# 5v_LP_Test_Mod.net
KiCad netlist of a schematic drawn in EAGLE
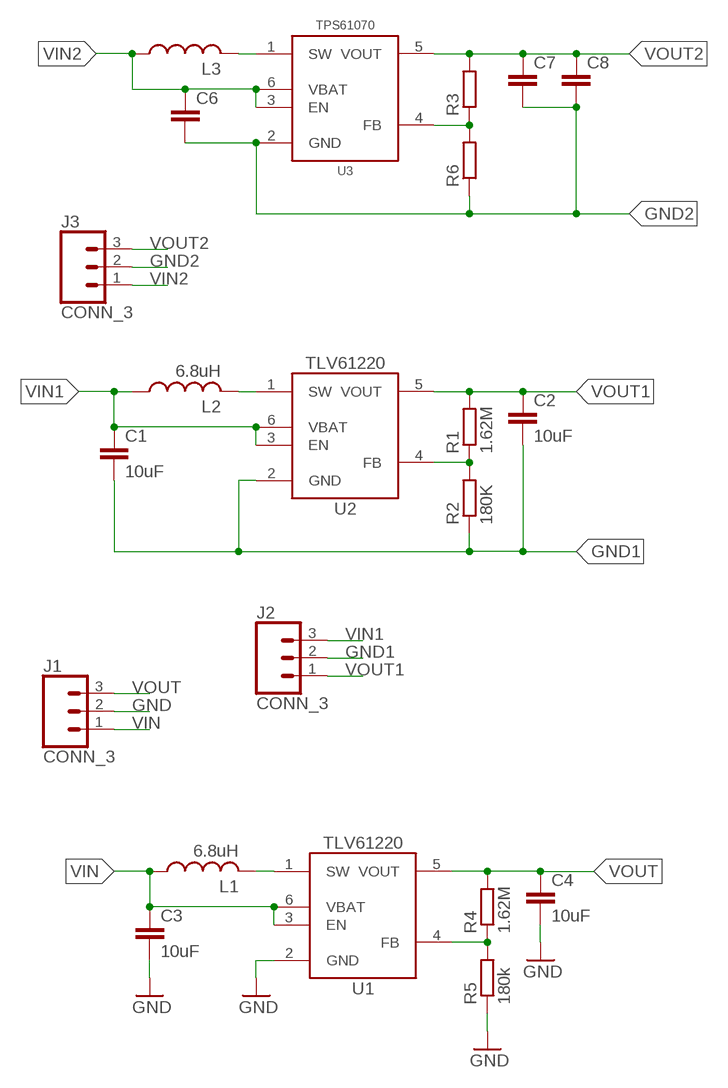
[diagram p0: schematic, sheet 1]

(export (version "E")
  (design (tool "Eeschema 10.0.6"))
  (components
    (comp (ref "C1")
      (value "10uF")
      (footprint "eagle-import:C0805")
      (fields (field (name "MF") "Murata") (field (name "MPN") "GRM21BR61C106KE15K"))
      (libsource (lib "eagle-import") (part "C-EUC080510UF"))
    )
    (comp (ref "C2")
      (value "10uF")
      (footprint "eagle-import:C0805")
      (fields (field (name "MF") "Murata") (field (name "MPN") "GRM21BR61C106KE15K"))
      (libsource (lib "eagle-import") (part "C-EUC080510UF"))
    )
    (comp (ref "C3")
      (value "10uF")
      (footprint "eagle-import:C0805")
      (fields (field (name "MF") "Murata") (field (name "MPN") "GRM21BR61C106KE15K"))
      (libsource (lib "eagle-import") (part "C-EUC080510UF"))
    )
    (comp (ref "C4")
      (value "10uF")
      (footprint "eagle-import:C0805")
      (fields (field (name "MF") "Murata") (field (name "MPN") "GRM21BR61C106KE15K"))
      (libsource (lib "eagle-import") (part "C-EUC080510UF"))
    )
    (comp (ref "C6")
      (value "C-EUC0805")
      (footprint "eagle-import:C0805")
      (libsource (lib "eagle-import") (part "C-EUC0805"))
    )
    (comp (ref "C7")
      (value "C-EUC0603")
      (footprint "eagle-import:C0603")
      (libsource (lib "eagle-import") (part "C-EUC0603"))
    )
    (comp (ref "C8")
      (value "C-EUC0603")
      (footprint "eagle-import:C0603")
      (libsource (lib "eagle-import") (part "C-EUC0603"))
    )
    (comp (ref "J1")
      (value "CONN_3")
      (footprint "eagle-import:1X03")
      (libsource (lib "eagle-import") (part "CONN_3"))
    )
    (comp (ref "J2")
      (value "CONN_3")
      (footprint "eagle-import:1X03")
      (libsource (lib "eagle-import") (part "CONN_3"))
    )
    (comp (ref "J3")
      (value "CONN_3")
      (footprint "eagle-import:1X03")
      (libsource (lib "eagle-import") (part "CONN_3"))
    )
    (comp (ref "L1")
      (value "6.8uH")
      (footprint "eagle-import:1008")
      (fields (field (name "MF") "Wurth") (field (name "MPN") "74438323068"))
      (libsource (lib "eagle-import") (part "INDUCTOR1008"))
    )
    (comp (ref "L2")
      (value "6.8uH")
      (footprint "eagle-import:1008")
      (libsource (lib "eagle-import") (part "INDUCTOR1008"))
    )
    (comp (ref "L3")
      (value "INDUCTORTPC_3.8X3.8")
      (footprint "eagle-import:WE-TPC(3.8X3.8)")
      (libsource (lib "eagle-import") (part "INDUCTORTPC_3.8X3.8"))
    )
    (comp (ref "R1")
      (value "1.62M")
      (footprint "eagle-import:R0603")
      (fields (field (name "MF") "Yageo"))
      (libsource (lib "eagle-import") (part "R-EU_R0603"))
    )
    (comp (ref "R2")
      (value "180K")
      (footprint "eagle-import:R0603")
      (fields (field (name "MF") "Yageo"))
      (libsource (lib "eagle-import") (part "R-EU_R0603"))
    )
    (comp (ref "R3")
      (value "R-EU_R0603")
      (footprint "eagle-import:R0603")
      (fields (field (name "MF") "Yageo"))
      (libsource (lib "eagle-import") (part "R-EU_R0603"))
    )
    (comp (ref "R4")
      (value "1.62M")
      (footprint "eagle-import:R0603")
      (fields (field (name "MF") "Stackpole") (field (name "MPN") "RMCF0603FT1M62"))
      (libsource (lib "eagle-import") (part "R-EU_R06031.62M"))
    )
    (comp (ref "R5")
      (value "180k")
      (footprint "eagle-import:R0603")
      (fields (field (name "MF") "Panasonic") (field (name "MPN") "ERJ-3EKF1803V"))
      (libsource (lib "eagle-import") (part "R-EU_R0603180K"))
    )
    (comp (ref "R6")
      (value "R-EU_R0603")
      (footprint "eagle-import:R0603")
      (fields (field (name "MF") "Yageo"))
      (libsource (lib "eagle-import") (part "R-EU_R0603"))
    )
    (comp (ref "U1")
      (value "TLV61220DBV")
      (footprint "eagle-import:DBV_R-PDSO-G6")
      (fields (field (name "MF") "TI") (field (name "MPN") "TLV61220DBVR"))
      (libsource (lib "eagle-import") (part "TLV61220DBV"))
    )
    (comp (ref "U2")
      (value "TLV61220DBV")
      (footprint "eagle-import:DBV_R-PDSO-G6")
      (fields (field (name "MF") "TI") (field (name "MPN") "TLV61220DBVR"))
      (libsource (lib "eagle-import") (part "TLV61220DBV"))
    )
    (comp (ref "U3")
      (value "TPS61070DDC")
      (footprint "eagle-import:DDC_R-PDSO-G6")
      (fields (field (name "DISP") "TPS61070") (field (name "MF") "TI") (field (name "MPN") "TPS61070DDCR"))
      (libsource (lib "eagle-import") (part "TPS6107DDC0"))
    )
  )
  (nets
    (net (code "1") (name "GND") (class "Default")
      (node (ref "C3") (pin "2") (pinfunction "2_2") (pintype "passive"))
      (node (ref "C4") (pin "2") (pinfunction "2_2") (pintype "passive"))
      (node (ref "J1") (pin "2") (pinfunction "2_2") (pintype "passive"))
      (node (ref "R5") (pin "1") (pinfunction "1_1") (pintype "passive"))
      (node (ref "U1") (pin "2") (pinfunction "GND_2") (pintype "power_in"))
    )
    (net (code "2") (name "GND1") (class "Default")
      (node (ref "C1") (pin "2") (pinfunction "2_2") (pintype "passive"))
      (node (ref "C2") (pin "2") (pinfunction "2_2") (pintype "passive"))
      (node (ref "J2") (pin "2") (pinfunction "2_2") (pintype "passive"))
      (node (ref "R2") (pin "1") (pinfunction "1_1") (pintype "passive"))
      (node (ref "U2") (pin "2") (pinfunction "GND_2") (pintype "power_in"))
    )
    (net (code "3") (name "GND2") (class "Default")
      (node (ref "C6") (pin "2") (pinfunction "2_2") (pintype "passive"))
      (node (ref "C7") (pin "2") (pinfunction "2_2") (pintype "passive"))
      (node (ref "C8") (pin "2") (pinfunction "2_2") (pintype "passive"))
      (node (ref "J3") (pin "2") (pinfunction "2_2") (pintype "passive"))
      (node (ref "R6") (pin "1") (pinfunction "1_1") (pintype "passive"))
      (node (ref "U3") (pin "2") (pinfunction "GND_2") (pintype "power_in"))
    )
    (net (code "4") (name "Net-(U1-FB)") (class "Default")
      (node (ref "R4") (pin "1") (pinfunction "1_1") (pintype "passive"))
      (node (ref "R5") (pin "2") (pinfunction "2_2") (pintype "passive"))
      (node (ref "U1") (pin "4") (pinfunction "FB_4") (pintype "input"))
    )
    (net (code "5") (name "Net-(U1-SW)") (class "Default")
      (node (ref "L1") (pin "2") (pinfunction "2_2") (pintype "passive"))
      (node (ref "U1") (pin "1") (pinfunction "SW_1") (pintype "power_in"))
    )
    (net (code "6") (name "Net-(U2-FB)") (class "Default")
      (node (ref "R1") (pin "1") (pinfunction "1_1") (pintype "passive"))
      (node (ref "R2") (pin "2") (pinfunction "2_2") (pintype "passive"))
      (node (ref "U2") (pin "4") (pinfunction "FB_4") (pintype "input"))
    )
    (net (code "7") (name "Net-(U2-SW)") (class "Default")
      (node (ref "L2") (pin "2") (pinfunction "2_2") (pintype "passive"))
      (node (ref "U2") (pin "1") (pinfunction "SW_1") (pintype "power_in"))
    )
    (net (code "8") (name "Net-(U3-FB)") (class "Default")
      (node (ref "R3") (pin "1") (pinfunction "1_1") (pintype "passive"))
      (node (ref "R6") (pin "2") (pinfunction "2_2") (pintype "passive"))
      (node (ref "U3") (pin "4") (pinfunction "FB_4") (pintype "input"))
    )
    (net (code "9") (name "Net-(U3-SW)") (class "Default")
      (node (ref "L3") (pin "2") (pinfunction "2_2") (pintype "passive"))
      (node (ref "U3") (pin "1") (pinfunction "SW_1") (pintype "input"))
    )
    (net (code "10") (name "VIN") (class "Default")
      (node (ref "C3") (pin "1") (pinfunction "1_1") (pintype "passive"))
      (node (ref "J1") (pin "1") (pinfunction "1_1") (pintype "passive"))
      (node (ref "L1") (pin "1") (pinfunction "1_1") (pintype "passive"))
      (node (ref "U1") (pin "3") (pinfunction "EN_3") (pintype "input"))
      (node (ref "U1") (pin "6") (pinfunction "VBAT_6") (pintype "power_in"))
    )
    (net (code "11") (name "VIN1") (class "Default")
      (node (ref "C1") (pin "1") (pinfunction "1_1") (pintype "passive"))
      (node (ref "J2") (pin "3") (pinfunction "3_3") (pintype "passive"))
      (node (ref "L2") (pin "1") (pinfunction "1_1") (pintype "passive"))
      (node (ref "U2") (pin "3") (pinfunction "EN_3") (pintype "input"))
      (node (ref "U2") (pin "6") (pinfunction "VBAT_6") (pintype "power_in"))
    )
    (net (code "12") (name "VIN2") (class "Default")
      (node (ref "C6") (pin "1") (pinfunction "1_1") (pintype "passive"))
      (node (ref "J3") (pin "1") (pinfunction "1_1") (pintype "passive"))
      (node (ref "L3") (pin "1") (pinfunction "1_1") (pintype "passive"))
      (node (ref "U3") (pin "3") (pinfunction "EN_3") (pintype "input"))
      (node (ref "U3") (pin "6") (pinfunction "VBAT_6") (pintype "power_in"))
    )
    (net (code "13") (name "VOUT") (class "Default")
      (node (ref "C4") (pin "1") (pinfunction "1_1") (pintype "passive"))
      (node (ref "J1") (pin "3") (pinfunction "3_3") (pintype "passive"))
      (node (ref "R4") (pin "2") (pinfunction "2_2") (pintype "passive"))
      (node (ref "U1") (pin "5") (pinfunction "VOUT_5") (pintype "power_in"))
    )
    (net (code "14") (name "VOUT1") (class "Default")
      (node (ref "C2") (pin "1") (pinfunction "1_1") (pintype "passive"))
      (node (ref "J2") (pin "1") (pinfunction "1_1") (pintype "passive"))
      (node (ref "R1") (pin "2") (pinfunction "2_2") (pintype "passive"))
      (node (ref "U2") (pin "5") (pinfunction "VOUT_5") (pintype "power_in"))
    )
    (net (code "15") (name "VOUT2") (class "Default")
      (node (ref "C7") (pin "1") (pinfunction "1_1") (pintype "passive"))
      (node (ref "C8") (pin "1") (pinfunction "1_1") (pintype "passive"))
      (node (ref "J3") (pin "3") (pinfunction "3_3") (pintype "passive"))
      (node (ref "R3") (pin "2") (pinfunction "2_2") (pintype "passive"))
      (node (ref "U3") (pin "5") (pinfunction "VOUT_5") (pintype "power_in"))
    )
  )
)
